# Connector_SOM40.net
KiCad netlist of a schematic drawn in Altium Designer
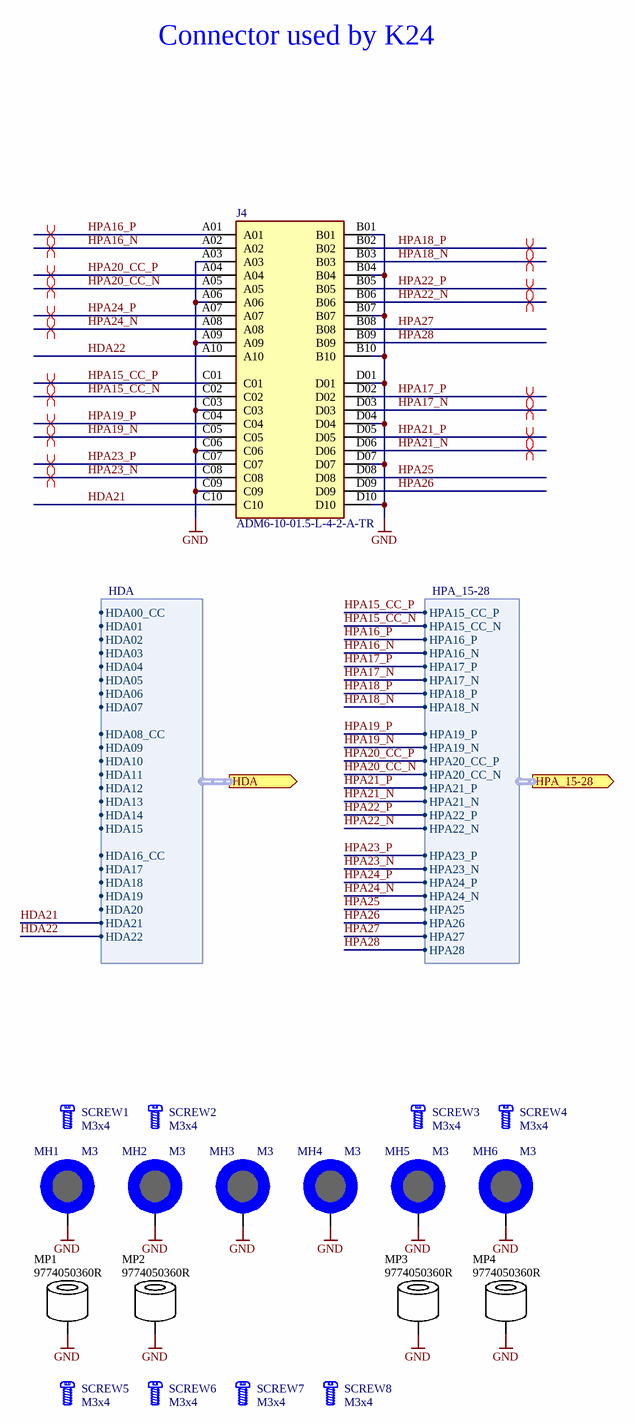
[diagram p0: Connector_SOM40.SchDoc]

(export (version "E")
  (design (tool "Eeschema 10.0.6"))
  (components
    (comp (ref "J4")
      (value "ADM6-10-01.5-L-4-2-A-TR")
      (footprint "SAMTEC_ADM6-10-01.5-L-4-2-A-TR")
      (fields (field (name "MANUFACTURER") "Samtec"))
      (libsource (lib "Simple_EEM_Controller") (part "ADM6-10-01.5-L-4-2-A-TR"))
    )
    (comp (ref "MH1")
      (value "M3")
      (footprint "MH-M3_COPPER")
      (description "Mounting hole, M3, exposed pad")
      (fields (field (name "AUTHOR") "KB"))
      (libsource (lib "Mechanical And PCB Features") (part "MH"))
    )
    (comp (ref "MH2")
      (value "M3")
      (footprint "MH-M3_COPPER")
      (description "Mounting hole, M3, exposed pad")
      (fields (field (name "AUTHOR") "KB"))
      (libsource (lib "Mechanical And PCB Features") (part "MH"))
    )
    (comp (ref "MH3")
      (value "M3")
      (footprint "MH-M3_COPPER")
      (description "Mounting hole, M3, exposed pad")
      (fields (field (name "AUTHOR") "KB"))
      (libsource (lib "Mechanical And PCB Features") (part "MH"))
    )
    (comp (ref "MH4")
      (value "M3")
      (footprint "MH-M3_COPPER")
      (description "Mounting hole, M3, exposed pad")
      (fields (field (name "AUTHOR") "KB"))
      (libsource (lib "Mechanical And PCB Features") (part "MH"))
    )
    (comp (ref "MH5")
      (value "M3")
      (footprint "MH-M3_COPPER")
      (description "Mounting hole, M3, exposed pad")
      (fields (field (name "AUTHOR") "KB"))
      (libsource (lib "Mechanical And PCB Features") (part "MH"))
    )
    (comp (ref "MH6")
      (value "M3")
      (footprint "MH-M3_COPPER")
      (description "Mounting hole, M3, exposed pad")
      (fields (field (name "AUTHOR") "KB"))
      (libsource (lib "Mechanical And PCB Features") (part "MH"))
    )
    (comp (ref "MP1")
      (value "9774050360R")
      (footprint "9774050960R")
      (description "MP")
      (fields (field (name "MANUFACTURER") "Würth Elektronik"))
      (libsource (lib "Simple_EEM_Controller") (part "9774050960R"))
    )
    (comp (ref "MP2")
      (value "9774050360R")
      (footprint "9774050960R")
      (description "MP")
      (fields (field (name "MANUFACTURER") "Würth Elektronik"))
      (libsource (lib "Simple_EEM_Controller") (part "9774050960R"))
    )
    (comp (ref "MP3")
      (value "9774050360R")
      (footprint "9774050960R")
      (description "MP")
      (fields (field (name "MANUFACTURER") "Würth Elektronik"))
      (libsource (lib "Simple_EEM_Controller") (part "9774050960R"))
    )
    (comp (ref "MP4")
      (value "9774050360R")
      (footprint "9774050960R")
      (description "MP")
      (fields (field (name "MANUFACTURER") "Würth Elektronik"))
      (libsource (lib "Simple_EEM_Controller") (part "9774050960R"))
    )
    (comp (ref "SCREW1")
      (value "M3x4")
      (footprint "KRAFTBERG_M3X4/ISO7380-1-A2-K26")
      (description "Screw")
      (fields
        (field (name "PART NUMBER") "KRAFTBERG_M3X4/ISO7380-1-A2")
        (field (name "MANUFACTURER") "KRAFTBERG")
        (field (name "AUTHOR") "CERN DEM JLC")
      )
      (libsource (lib "Simple_EEM_Controller") (part "Screw"))
    )
    (comp (ref "SCREW2")
      (value "M3x4")
      (footprint "KRAFTBERG_M3X4/ISO7380-1-A2-K26")
      (description "Screw")
      (fields
        (field (name "PART NUMBER") "KRAFTBERG_M3X4/ISO7380-1-A2")
        (field (name "MANUFACTURER") "KRAFTBERG")
        (field (name "AUTHOR") "CERN DEM JLC")
      )
      (libsource (lib "Simple_EEM_Controller") (part "Screw"))
    )
    (comp (ref "SCREW3")
      (value "M3x4")
      (footprint "KRAFTBERG_M3X4/ISO7380-1-A2-K26")
      (description "Screw")
      (fields
        (field (name "PART NUMBER") "KRAFTBERG_M3X4/ISO7380-1-A2")
        (field (name "MANUFACTURER") "KRAFTBERG")
        (field (name "AUTHOR") "CERN DEM JLC")
      )
      (libsource (lib "Simple_EEM_Controller") (part "Screw"))
    )
    (comp (ref "SCREW4")
      (value "M3x4")
      (footprint "KRAFTBERG_M3X4/ISO7380-1-A2-K26")
      (description "Screw")
      (fields
        (field (name "PART NUMBER") "KRAFTBERG_M3X4/ISO7380-1-A2")
        (field (name "MANUFACTURER") "KRAFTBERG")
        (field (name "AUTHOR") "CERN DEM JLC")
      )
      (libsource (lib "Simple_EEM_Controller") (part "Screw"))
    )
    (comp (ref "SCREW5")
      (value "M3x4")
      (footprint "KRAFTBERG_M3X4/ISO7380-1-A2-K24")
      (description "Screw")
      (fields
        (field (name "PART NUMBER") "KRAFTBERG_M3X4/ISO7380-1-A2")
        (field (name "MANUFACTURER") "KRAFTBERG")
        (field (name "AUTHOR") "CERN DEM JLC")
      )
      (libsource (lib "Simple_EEM_Controller") (part "Screw"))
    )
    (comp (ref "SCREW6")
      (value "M3x4")
      (footprint "KRAFTBERG_M3X4/ISO7380-1-A2-K24")
      (description "Screw")
      (fields
        (field (name "PART NUMBER") "KRAFTBERG_M3X4/ISO7380-1-A2")
        (field (name "MANUFACTURER") "KRAFTBERG")
        (field (name "AUTHOR") "CERN DEM JLC")
      )
      (libsource (lib "Simple_EEM_Controller") (part "Screw"))
    )
    (comp (ref "SCREW7")
      (value "M3x4")
      (footprint "KRAFTBERG_M3X4/ISO7380-1-A2-K24")
      (description "Screw")
      (fields
        (field (name "PART NUMBER") "KRAFTBERG_M3X4/ISO7380-1-A2")
        (field (name "MANUFACTURER") "KRAFTBERG")
        (field (name "AUTHOR") "CERN DEM JLC")
      )
      (libsource (lib "Simple_EEM_Controller") (part "Screw"))
    )
    (comp (ref "SCREW8")
      (value "M3x4")
      (footprint "KRAFTBERG_M3X4/ISO7380-1-A2-K24")
      (description "Screw")
      (fields
        (field (name "PART NUMBER") "KRAFTBERG_M3X4/ISO7380-1-A2")
        (field (name "MANUFACTURER") "KRAFTBERG")
        (field (name "AUTHOR") "CERN DEM JLC")
      )
      (libsource (lib "Simple_EEM_Controller") (part "Screw"))
    )
  )
  (nets
    (net (code "3") (name "/HDA21") (class "Default")
      (node (ref "J4") (pin "C10") (pinfunction "C10_C10") (pintype "passive"))
    )
    (net (code "4") (name "/HDA22") (class "Default")
      (node (ref "J4") (pin "A10") (pinfunction "A10_A10") (pintype "passive"))
    )
    (net (code "5") (name "/HPA15_CC_N") (class "Default")
      (node (ref "J4") (pin "C02") (pinfunction "C02_C02") (pintype "passive"))
    )
    (net (code "6") (name "/HPA15_CC_P") (class "Default")
      (node (ref "J4") (pin "C01") (pinfunction "C01_C01") (pintype "passive"))
    )
    (net (code "7") (name "/HPA16_N") (class "Default")
      (node (ref "J4") (pin "A02") (pinfunction "A02_A02") (pintype "passive"))
    )
    (net (code "8") (name "/HPA16_P") (class "Default")
      (node (ref "J4") (pin "A01") (pinfunction "A01_A01") (pintype "passive"))
    )
    (net (code "9") (name "/HPA17_N") (class "Default")
      (node (ref "J4") (pin "D03") (pinfunction "D03_D03") (pintype "passive"))
    )
    (net (code "10") (name "/HPA17_P") (class "Default")
      (node (ref "J4") (pin "D02") (pinfunction "D02_D02") (pintype "passive"))
    )
    (net (code "11") (name "/HPA18_N") (class "Default")
      (node (ref "J4") (pin "B03") (pinfunction "B03_B03") (pintype "passive"))
    )
    (net (code "12") (name "/HPA18_P") (class "Default")
      (node (ref "J4") (pin "B02") (pinfunction "B02_B02") (pintype "passive"))
    )
    (net (code "13") (name "/HPA19_N") (class "Default")
      (node (ref "J4") (pin "C05") (pinfunction "C05_C05") (pintype "passive"))
    )
    (net (code "14") (name "/HPA19_P") (class "Default")
      (node (ref "J4") (pin "C04") (pinfunction "C04_C04") (pintype "passive"))
    )
    (net (code "15") (name "/HPA20_CC_N") (class "Default")
      (node (ref "J4") (pin "A05") (pinfunction "A05_A05") (pintype "passive"))
    )
    (net (code "16") (name "/HPA20_CC_P") (class "Default")
      (node (ref "J4") (pin "A04") (pinfunction "A04_A04") (pintype "passive"))
    )
    (net (code "17") (name "/HPA21_N") (class "Default")
      (node (ref "J4") (pin "D06") (pinfunction "D06_D06") (pintype "passive"))
    )
    (net (code "18") (name "/HPA21_P") (class "Default")
      (node (ref "J4") (pin "D05") (pinfunction "D05_D05") (pintype "passive"))
    )
    (net (code "19") (name "/HPA22_N") (class "Default")
      (node (ref "J4") (pin "B06") (pinfunction "B06_B06") (pintype "passive"))
    )
    (net (code "20") (name "/HPA22_P") (class "Default")
      (node (ref "J4") (pin "B05") (pinfunction "B05_B05") (pintype "passive"))
    )
    (net (code "21") (name "/HPA23_N") (class "Default")
      (node (ref "J4") (pin "C08") (pinfunction "C08_C08") (pintype "passive"))
    )
    (net (code "22") (name "/HPA23_P") (class "Default")
      (node (ref "J4") (pin "C07") (pinfunction "C07_C07") (pintype "passive"))
    )
    (net (code "23") (name "/HPA24_N") (class "Default")
      (node (ref "J4") (pin "A08") (pinfunction "A08_A08") (pintype "passive"))
    )
    (net (code "24") (name "/HPA24_P") (class "Default")
      (node (ref "J4") (pin "A07") (pinfunction "A07_A07") (pintype "passive"))
    )
    (net (code "25") (name "/HPA25") (class "Default")
      (node (ref "J4") (pin "D08") (pinfunction "D08_D08") (pintype "passive"))
    )
    (net (code "26") (name "/HPA26") (class "Default")
      (node (ref "J4") (pin "D09") (pinfunction "D09_D09") (pintype "passive"))
    )
    (net (code "27") (name "/HPA27") (class "Default")
      (node (ref "J4") (pin "B08") (pinfunction "B08_B08") (pintype "passive"))
    )
    (net (code "28") (name "/HPA28") (class "Default")
      (node (ref "J4") (pin "B09") (pinfunction "B09_B09") (pintype "passive"))
    )
    (net (code "31") (name "GND") (class "Default")
      (node (ref "J4") (pin "A03") (pinfunction "A03_A03") (pintype "passive"))
      (node (ref "J4") (pin "A06") (pinfunction "A06_A06") (pintype "passive"))
      (node (ref "J4") (pin "A09") (pinfunction "A09_A09") (pintype "passive"))
      (node (ref "J4") (pin "B01") (pinfunction "B01_B01") (pintype "passive"))
      (node (ref "J4") (pin "B04") (pinfunction "B04_B04") (pintype "passive"))
      (node (ref "J4") (pin "B07") (pinfunction "B07_B07") (pintype "passive"))
      (node (ref "J4") (pin "B10") (pinfunction "B10_B10") (pintype "passive"))
      (node (ref "J4") (pin "C03") (pinfunction "C03_C03") (pintype "passive"))
      (node (ref "J4") (pin "C06") (pinfunction "C06_C06") (pintype "passive"))
      (node (ref "J4") (pin "C09") (pinfunction "C09_C09") (pintype "passive"))
      (node (ref "J4") (pin "D01") (pinfunction "D01_D01") (pintype "passive"))
      (node (ref "J4") (pin "D04") (pinfunction "D04_D04") (pintype "passive"))
      (node (ref "J4") (pin "D07") (pinfunction "D07_D07") (pintype "passive"))
      (node (ref "J4") (pin "D10") (pinfunction "D10_D10") (pintype "passive"))
      (node (ref "MH1") (pin "MH") (pinfunction "MH_MH") (pintype "passive"))
      (node (ref "MH2") (pin "MH") (pinfunction "MH_MH") (pintype "passive"))
      (node (ref "MH3") (pin "MH") (pinfunction "MH_MH") (pintype "passive"))
      (node (ref "MH4") (pin "MH") (pinfunction "MH_MH") (pintype "passive"))
      (node (ref "MH5") (pin "MH") (pinfunction "MH_MH") (pintype "passive"))
      (node (ref "MH6") (pin "MH") (pinfunction "MH_MH") (pintype "passive"))
      (node (ref "MP1") (pin "1") (pinfunction "1_1") (pintype "passive"))
      (node (ref "MP2") (pin "1") (pinfunction "1_1") (pintype "passive"))
      (node (ref "MP3") (pin "1") (pinfunction "1_1") (pintype "passive"))
      (node (ref "MP4") (pin "1") (pinfunction "1_1") (pintype "passive"))
    )
  )
)
